# level_shifter.net
KiCad netlist of a schematic drawn in Altium Designer
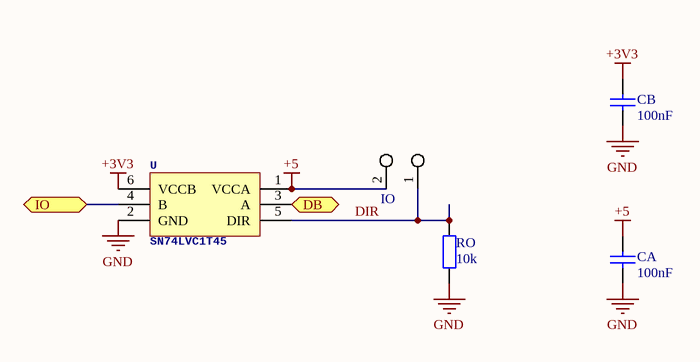
[diagram p0: level_shifter.SchDoc]

(export (version "E")
  (design (tool "Eeschema 10.0.6"))
  (components
    (comp (ref "CA")
      (value "100nF")
      (footprint "CAP 0402/1005 RF")
      (description "Capacitor Non-Polarized Generic")
      (fields (field (name "Comment") "Capacitor"))
      (libsource (lib "BB_Passives") (part "Capacitor"))
    )
    (comp (ref "CB")
      (value "100nF")
      (footprint "CAP 0402/1005 RF")
      (description "Capacitor Non-Polarized Generic")
      (fields (field (name "Comment") "Capacitor"))
      (libsource (lib "BB_Passives") (part "Capacitor"))
    )
    (comp (ref "IO")
      (value "Header 1x2")
      (footprint "Header 1x2 100mil Vertical")
      (description "Standard Header Connector")
      (libsource (lib "BB_Connectors") (part "Header 1x2"))
    )
    (comp (ref "RO")
      (value "10k")
      (footprint "RES 0402/1005 RF")
      (description "Resistor EU Generic")
      (fields (field (name "Comment") "Resistor"))
      (libsource (lib "BB_Passives") (part "Resistor"))
    )
    (comp (ref "U")
      (value "SN74LVC1T45")
      (footprint "SOT65P210X110-6N")
      (description "Level Shifter with DIR, Single-Bit, Dual-Supply, Automotive")
      (fields (field (name "MFR") "Texas Instruments"))
      (libsource (lib "BB_DigitalIC") (part "SN74LVC1T45"))
    )
  )
  (nets
    (net (code "1") (name "+3V3") (class "Default")
      (node (ref "CB") (pin "2") (pinfunction "2_2") (pintype "passive"))
      (node (ref "U") (pin "6") (pinfunction "VCCB_6") (pintype "passive"))
    )
    (net (code "2") (name "+5") (class "Default")
      (node (ref "CA") (pin "2") (pinfunction "2_2") (pintype "passive"))
      (node (ref "IO") (pin "2") (pinfunction "2_2") (pintype "passive"))
      (node (ref "U") (pin "1") (pinfunction "VCCA_1") (pintype "passive"))
    )
    (net (code "3") (name "/DB") (class "Default")
      (node (ref "U") (pin "3") (pinfunction "A_3") (pintype "passive"))
    )
    (net (code "4") (name "/DIR") (class "Default")
      (node (ref "IO") (pin "1") (pinfunction "1_1") (pintype "passive"))
      (node (ref "RO") (pin "1") (pinfunction "1_1") (pintype "passive"))
      (node (ref "U") (pin "5") (pinfunction "DIR_5") (pintype "passive"))
    )
    (net (code "5") (name "/IO") (class "Default")
      (node (ref "U") (pin "4") (pinfunction "B_4") (pintype "passive"))
    )
    (net (code "6") (name "GND") (class "Default")
      (node (ref "CA") (pin "1") (pinfunction "1_1") (pintype "passive"))
      (node (ref "CB") (pin "1") (pinfunction "1_1") (pintype "passive"))
      (node (ref "RO") (pin "2") (pinfunction "2_2") (pintype "passive"))
      (node (ref "U") (pin "2") (pinfunction "GND_2") (pintype "passive"))
    )
  )
)
